# bmsMaster_power.net
KiCad netlist of a schematic drawn in Altium Designer
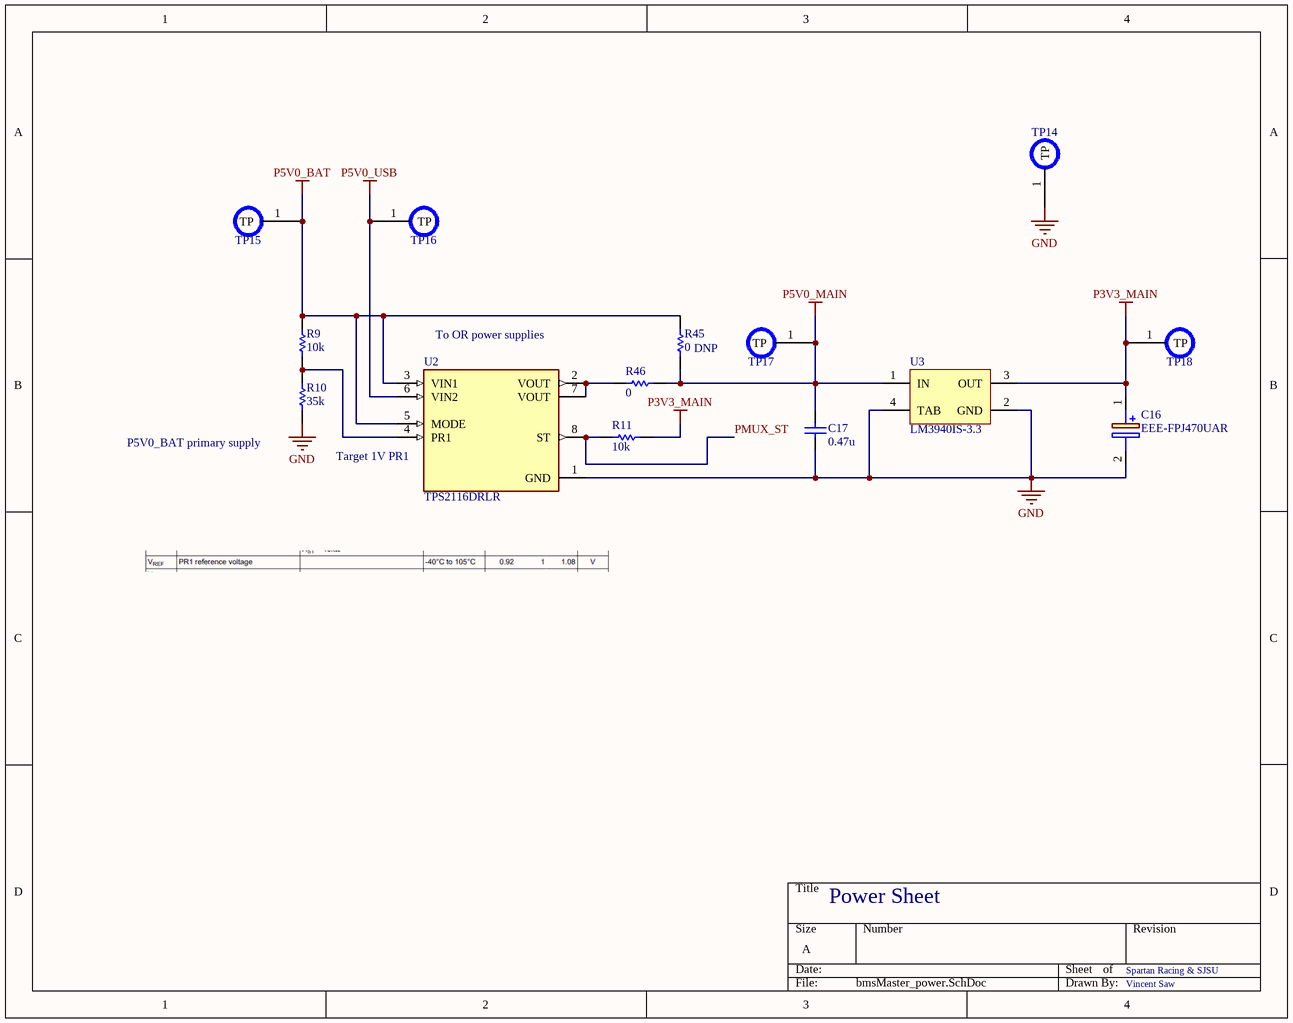
[diagram p0: bmsMaster_power.SchDoc]

(export (version "E")
  (design (tool "Eeschema 10.0.6"))
  (components
    (comp (ref "C16")
      (value "EEE-FPJ470UAR")
      (footprint "SamacSys:EEE1AA220WR")
      (description "Capacitor Polarised")
      (fields (field (name "MOUSER PART NUMBER") "667-EEE-FPJ470UAR"))
      (libsource (lib "*") (part "EEE-FPJ470UAR"))
    )
    (comp (ref "C17")
      (value "0.47u")
      (footprint "CAPC1608X90N")
      (description "Capacitor")
      (libsource (lib "Simulation Generic Components") (part "Capacitor"))
    )
    (comp (ref "R9")
      (value "10k")
      (footprint "RESC1608X50N")
      (description "Resistor")
      (libsource (lib "Simulation Generic Components") (part "Resistor"))
    )
    (comp (ref "R10")
      (value "35k")
      (footprint "RESC1608X50N")
      (description "Resistor")
      (libsource (lib "Simulation Generic Components") (part "Resistor"))
    )
    (comp (ref "R11")
      (value "10k")
      (footprint "RESC1608X50N")
      (description "Resistor")
      (libsource (lib "Simulation Generic Components") (part "Resistor"))
    )
    (comp (ref "R45")
      (value "0")
      (footprint "RESC1608X50N")
      (description "Resistor")
      (libsource (lib "Simulation Generic Components") (part "Resistor"))
    )
    (comp (ref "R46")
      (value "0")
      (footprint "RESC1608X50N")
      (description "Resistor")
      (libsource (lib "Simulation Generic Components") (part "Resistor"))
    )
    (comp (ref "TP14")
      (value "TSTPT")
      (footprint "Testpoint1")
      (libsource (lib "testpoint1") (part "Testpoint1"))
    )
    (comp (ref "TP15")
      (value "TSTPT")
      (footprint "Testpoint1")
      (libsource (lib "testpoint1") (part "Testpoint1"))
    )
    (comp (ref "TP16")
      (value "TSTPT")
      (footprint "Testpoint1")
      (libsource (lib "testpoint1") (part "Testpoint1"))
    )
    (comp (ref "TP17")
      (value "TSTPT")
      (footprint "Testpoint1")
      (libsource (lib "testpoint1") (part "Testpoint1"))
    )
    (comp (ref "TP18")
      (value "TSTPT")
      (footprint "Testpoint1")
      (libsource (lib "testpoint1") (part "Testpoint1"))
    )
    (comp (ref "U2")
      (value "TPS2116DRLR")
      (footprint "TPS2116DRLR:SOTFL50P160X60-8N")
      (description "1.6 V to 5.5 V, 2.5-A Low IQ Power Mux with Manual and Priority Switchover")
      (fields (field (name "MF") "{'manufacturer': u'Texas Instruments'}"))
      (libsource (lib "TPS2116DRLR") (part "TPS2116DRLR"))
    )
    (comp (ref "U3")
      (value "LM3940IS-3.3")
      (footprint "KTT0003B_N")
      (description "1A Low Dropout Regulator for 5V to 3.3V Conversion, 3-pin TO-263")
      (fields (field (name "MANUFACTURER") "Texas Instruments"))
      (libsource (lib "Altium Content Vault") (part "PM-REG-LM2940-TO4"))
    )
  )
  (nets
    (net (code "1") (name "/PMUX_ST") (class "Default")
      (node (ref "R11") (pin "2") (pinfunction "2_2") (pintype "passive"))
      (node (ref "U2") (pin "8") (pinfunction "ST_8") (pintype "output"))
    )
    (net (code "2") (name "GND") (class "Default")
      (node (ref "C16") (pin "2") (pinfunction "-_2") (pintype "passive"))
      (node (ref "C17") (pin "1") (pinfunction "1_1") (pintype "passive"))
      (node (ref "R10") (pin "1") (pinfunction "1_1") (pintype "passive"))
      (node (ref "TP14") (pin "1") (pinfunction "TP_1") (pintype "passive"))
      (node (ref "U2") (pin "1") (pinfunction "GND_1") (pintype "power_in"))
      (node (ref "U3") (pin "2") (pinfunction "GND_2") (pintype "power_in"))
      (node (ref "U3") (pin "4") (pinfunction "TAB_4") (pintype "power_in"))
    )
    (net (code "3") (name "Net-(R46-Pad1)") (class "Default")
      (node (ref "R46") (pin "1") (pinfunction "1_1") (pintype "passive"))
      (node (ref "U2") (pin "2") (pinfunction "VOUT_2") (pintype "output"))
      (node (ref "U2") (pin "7") (pinfunction "VOUT_7") (pintype "passive"))
    )
    (net (code "4") (name "Net-(U2-PR1)") (class "Default")
      (node (ref "R10") (pin "2") (pinfunction "2_2") (pintype "passive"))
      (node (ref "R9") (pin "1") (pinfunction "1_1") (pintype "passive"))
      (node (ref "U2") (pin "4") (pinfunction "PR1_4") (pintype "input"))
    )
    (net (code "5") (name "P3V3_MAIN") (class "Default")
      (node (ref "C16") (pin "1") (pinfunction "+_1") (pintype "passive"))
      (node (ref "R11") (pin "1") (pinfunction "1_1") (pintype "passive"))
      (node (ref "TP18") (pin "1") (pinfunction "TP_1") (pintype "passive"))
      (node (ref "U3") (pin "3") (pinfunction "OUT_3") (pintype "power_in"))
    )
    (net (code "6") (name "P5V0_BAT") (class "Default")
      (node (ref "R45") (pin "2") (pinfunction "2_2") (pintype "passive"))
      (node (ref "R9") (pin "2") (pinfunction "2_2") (pintype "passive"))
      (node (ref "TP15") (pin "1") (pinfunction "TP_1") (pintype "passive"))
      (node (ref "U2") (pin "3") (pinfunction "VIN1_3") (pintype "input"))
      (node (ref "U2") (pin "5") (pinfunction "MODE_5") (pintype "input"))
    )
    (net (code "7") (name "P5V0_MAIN") (class "Default")
      (node (ref "C17") (pin "2") (pinfunction "2_2") (pintype "passive"))
      (node (ref "R45") (pin "1") (pinfunction "1_1") (pintype "passive"))
      (node (ref "R46") (pin "2") (pinfunction "2_2") (pintype "passive"))
      (node (ref "TP17") (pin "1") (pinfunction "TP_1") (pintype "passive"))
      (node (ref "U3") (pin "1") (pinfunction "IN_1") (pintype "power_in"))
    )
    (net (code "8") (name "P5V0_USB") (class "Default")
      (node (ref "TP16") (pin "1") (pinfunction "TP_1") (pintype "passive"))
      (node (ref "U2") (pin "6") (pinfunction "VIN2_6") (pintype "input"))
    )
  )
)
